# 78l06.net
KiCad netlist of a schematic drawn in Altium Designer
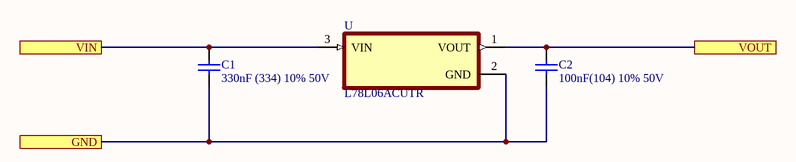
[diagram p0: 78l06.SchDoc]

(export (version "E")
  (design (tool "Eeschema 10.0.6"))
  (components
    (comp (ref "C1")
      (value "330nF (334) 10% 50V")
      (footprint "0805_C")
      (description "贴片电容")
      (libsource (lib "Miscellaneous Devices LC") (part "0805 330nF (334) 10% 50V"))
    )
    (comp (ref "C2")
      (value "100nF(104) 10% 50V")
      (footprint "0805_C")
      (description "贴片电容")
      (libsource (lib "Miscellaneous Devices LC") (part "0805 100nF(104) 10% 50V"))
    )
    (comp (ref "U")
      (value "L78L06ACUTR")
      (footprint "VREG_L78L12ABUTR")
      (description "Linear Voltage Regulator IC 1 Output 100mA SOT-89-3")
      (fields (field (name "MF") "STMicroelectronics"))
      (libsource (lib "L78L06ACUTR") (part "L78L06ACUTR"))
    )
  )
  (nets
    (net (code "1") (name "/GND") (class "Default")
      (node (ref "C1") (pin "1") (pinfunction "1_1") (pintype "passive"))
      (node (ref "C2") (pin "1") (pinfunction "1_1") (pintype "passive"))
      (node (ref "U") (pin "2") (pinfunction "GND_2") (pintype "power_in"))
    )
    (net (code "2") (name "/VIN") (class "Default")
      (node (ref "C1") (pin "2") (pinfunction "2_2") (pintype "passive"))
      (node (ref "U") (pin "3") (pinfunction "VIN_3") (pintype "input"))
    )
    (net (code "3") (name "/VOUT") (class "Default")
      (node (ref "C2") (pin "2") (pinfunction "2_2") (pintype "passive"))
      (node (ref "U") (pin "1") (pinfunction "VOUT_1") (pintype "output"))
    )
  )
)
